# APC.net
KiCad netlist of a schematic drawn in EAGLE
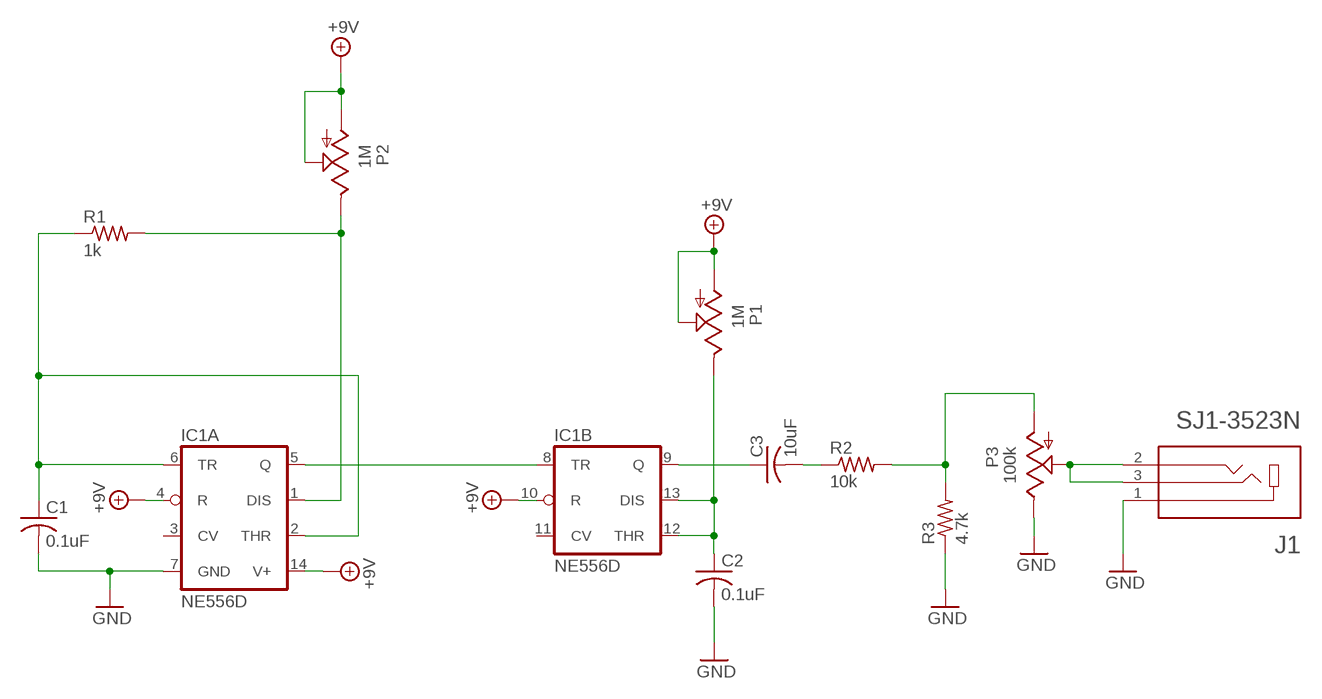
[diagram p0: schematic, sheet 1]

(export (version "E")
  (design (tool "Eeschema 10.0.6"))
  (components
    (comp (ref "C1")
      (value "0.1uF")
      (footprint "eagle-import:C0805")
      (libsource (lib "eagle-import") (part "C-USC0805"))
    )
    (comp (ref "C2")
      (value "0.1uF")
      (footprint "eagle-import:C0805")
      (libsource (lib "eagle-import") (part "C-USC0805"))
    )
    (comp (ref "C3")
      (value "10uF")
      (footprint "eagle-import:C0805")
      (libsource (lib "eagle-import") (part "C-USC0805"))
    )
    (comp (ref "IC1")
      (value "NE556D")
      (footprint "eagle-import:SO14")
      (libsource (lib "eagle-import") (part "556DNE"))
    )
    (comp (ref "J1")
      (value "SJ1-3523N")
      (footprint "eagle-import:CUI_SJ1-3523N")
      (fields (field (name "DIGI-KEY_PART_NUMBER") "CP1-3523NG-ND") (field (name "MF") "CUI Devices"))
      (libsource (lib "eagle-import") (part "SJ1-3523N"))
    )
    (comp (ref "P1")
      (value "1M")
      (footprint "eagle-import:PT-10")
      (libsource (lib "eagle-import") (part "TRIM_US-PT10"))
    )
    (comp (ref "P2")
      (value "1M")
      (footprint "eagle-import:PT-10")
      (libsource (lib "eagle-import") (part "TRIM_US-PT10"))
    )
    (comp (ref "P3")
      (value "100k")
      (footprint "eagle-import:PT-10")
      (libsource (lib "eagle-import") (part "TRIM_US-PT10"))
    )
    (comp (ref "R1")
      (value "1k")
      (footprint "eagle-import:R0805")
      (libsource (lib "eagle-import") (part "R-US_R0805"))
    )
    (comp (ref "R2")
      (value "10k")
      (footprint "eagle-import:R0805")
      (libsource (lib "eagle-import") (part "R-US_R0805"))
    )
    (comp (ref "R3")
      (value "4.7k")
      (footprint "eagle-import:R0805")
      (libsource (lib "eagle-import") (part "R-US_R0805"))
    )
  )
  (nets
    (net (code "1") (name "+9V") (class "Default")
      (node (ref "IC1") (pin "10") (pinfunction "R_10") (pintype "input"))
      (node (ref "IC1") (pin "14") (pinfunction "V+_14") (pintype "power_in"))
      (node (ref "IC1") (pin "4") (pinfunction "R_4") (pintype "input"))
      (node (ref "P1") (pin "A") (pinfunction "A_A") (pintype "passive"))
      (node (ref "P1") (pin "S") (pinfunction "S_S") (pintype "passive"))
      (node (ref "P2") (pin "A") (pinfunction "A_A") (pintype "passive"))
      (node (ref "P2") (pin "S") (pinfunction "S_S") (pintype "passive"))
    )
    (net (code "2") (name "GND") (class "Default")
      (node (ref "C1") (pin "2") (pinfunction "2_2") (pintype "passive"))
      (node (ref "C2") (pin "2") (pinfunction "2_2") (pintype "passive"))
      (node (ref "IC1") (pin "7") (pinfunction "GND_7") (pintype "power_in"))
      (node (ref "J1") (pin "1") (pinfunction "1_1") (pintype "passive"))
      (node (ref "P3") (pin "E") (pinfunction "E_E") (pintype "passive"))
      (node (ref "R3") (pin "1") (pinfunction "1_1") (pintype "passive"))
    )
    (net (code "3") (name "Net-(C3-Pad2)") (class "Default")
      (node (ref "C3") (pin "2") (pinfunction "2_2") (pintype "passive"))
      (node (ref "R2") (pin "1") (pinfunction "1_1") (pintype "passive"))
    )
    (net (code "4") (name "Net-(IC1A-DIS)") (class "Default")
      (node (ref "IC1") (pin "1") (pinfunction "DIS_1") (pintype "input"))
      (node (ref "P2") (pin "E") (pinfunction "E_E") (pintype "passive"))
      (node (ref "R1") (pin "2") (pinfunction "2_2") (pintype "passive"))
    )
    (net (code "5") (name "Net-(IC1A-Q)") (class "Default")
      (node (ref "IC1") (pin "5") (pinfunction "Q_5") (pintype "output"))
      (node (ref "IC1") (pin "8") (pinfunction "TR_8") (pintype "input"))
    )
    (net (code "6") (name "Net-(IC1A-THR)") (class "Default")
      (node (ref "C1") (pin "1") (pinfunction "1_1") (pintype "passive"))
      (node (ref "IC1") (pin "2") (pinfunction "THR_2") (pintype "input"))
      (node (ref "IC1") (pin "6") (pinfunction "TR_6") (pintype "input"))
      (node (ref "R1") (pin "1") (pinfunction "1_1") (pintype "passive"))
    )
    (net (code "7") (name "Net-(IC1B-DIS)") (class "Default")
      (node (ref "C2") (pin "1") (pinfunction "1_1") (pintype "passive"))
      (node (ref "IC1") (pin "12") (pinfunction "THR_12") (pintype "input"))
      (node (ref "IC1") (pin "13") (pinfunction "DIS_13") (pintype "input"))
      (node (ref "P1") (pin "E") (pinfunction "E_E") (pintype "passive"))
    )
    (net (code "8") (name "Net-(IC1B-Q)") (class "Default")
      (node (ref "C3") (pin "1") (pinfunction "1_1") (pintype "passive"))
      (node (ref "IC1") (pin "9") (pinfunction "Q_9") (pintype "output"))
    )
    (net (code "9") (name "Net-(J1-Pad2)") (class "Default")
      (node (ref "J1") (pin "2") (pinfunction "2_2") (pintype "passive"))
      (node (ref "J1") (pin "3") (pinfunction "3_3") (pintype "passive"))
      (node (ref "P3") (pin "S") (pinfunction "S_S") (pintype "passive"))
    )
    (net (code "10") (name "Net-(P3-PadA)") (class "Default")
      (node (ref "P3") (pin "A") (pinfunction "A_A") (pintype "passive"))
      (node (ref "R2") (pin "2") (pinfunction "2_2") (pintype "passive"))
      (node (ref "R3") (pin "2") (pinfunction "2_2") (pintype "passive"))
    )
    (net (code "11") (name "unconnected-(IC1A-CV-Pad3)") (class "Default")
      (node (ref "IC1") (pin "3") (pinfunction "CV_3") (pintype "input"))
    )
    (net (code "12") (name "unconnected-(IC1B-CV-Pad11)") (class "Default")
      (node (ref "IC1") (pin "11") (pinfunction "CV_11") (pintype "input"))
    )
  )
)
